# Cam.net
KiCad netlist of a schematic drawn in Altium Designer
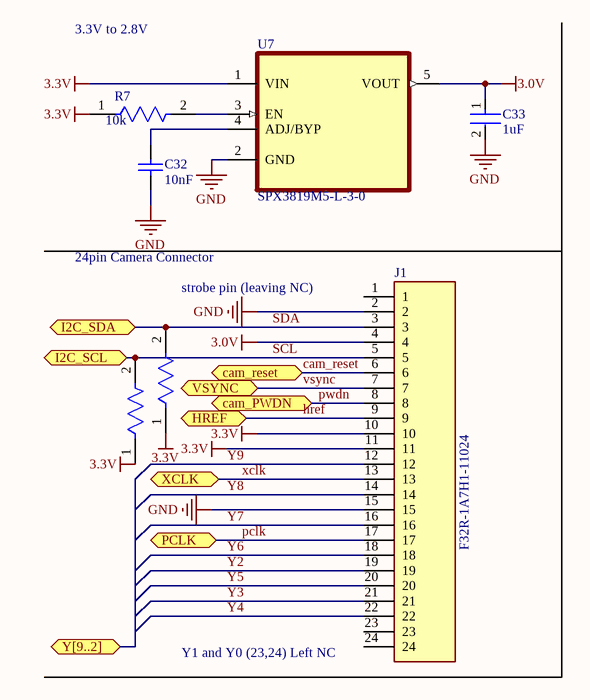
[diagram p0: Cam.SchDoc]

(export (version "E")
  (design (tool "Eeschema 10.0.6"))
  (components
    (comp (ref "C32")
      (value "10nF")
      (footprint "CAPC2013X140X50LL20T25")
      (fields
        (field (name "PART NUMBER") "08055F103KAT2A")
        (field (name "MANUFACTURER") "AVX Interconnect / Elco")
      )
      (libsource (lib "Altium Content Vault") (part "CAP"))
    )
    (comp (ref "C33")
      (value "1uF")
      (footprint "FP-RCE1K1-MFG")
      (description "RCEC72A105K1K1H03B")
      (fields (field (name "TOLERANCE") "10%"))
      (libsource (lib "Altium Content Vault") (part "RCEC72A105K1K1H03B"))
    )
    (comp (ref "J1")
      (value "F32R-1A7H1-11024")
      (footprint "AMPHENOL_F32R-1A7H1-11024")
      (fields (field (name "MF") "Amphenol ICC / Aorora"))
      (libsource (lib "George Evanisko") (part "F32R-1A7H1-11024"))
    )
    (comp (ref "R7")
      (value "10k")
      (footprint "FP-CPF0603-MFG")
      (description "RES SMD 10KΩ 0.5% 1/16W 0603")
      (fields
        (field (name "OCTOPART") "https://octopart.com/cpf0603d10ke-te+connectivity-22737789")
        (field (name "MANUFACTURER") "TE Connectivity")
      )
      (libsource (lib "Altium Content Vault") (part "1029c3af85768c4190bb7ad29bc67b5"))
    )
    (comp (ref "R11")
      (value "AC0603JR-7W10KL")
      (footprint "FP-AC0603-IPC_A")
      (description "RES 10kΩ 5.00% 0.2W 0603")
      (libsource (lib "Altium Content Vault") (part "1029c3af85768c4190bb7ad29bc67b5"))
    )
    (comp (ref "R12")
      (value "AC0603JR-7W10KL")
      (footprint "FP-AC0603-IPC_A")
      (description "RES 10kΩ 5.00% 0.2W 0603")
      (libsource (lib "Altium Content Vault") (part "1029c3af85768c4190bb7ad29bc67b5"))
    )
    (comp (ref "U7")
      (value "SPX3819M5-L-3-0")
      (footprint "SOT95P280X145-5N")
      (description "Linear Voltage Regulator IC Positive Fixed 1 Output 500mA SOT-23-5")
      (fields (field (name "MF") "MaxLinear, Inc."))
      (libsource (lib "George Evanisko") (part "SPX3819M5-L-3-0"))
    )
  )
  (nets
    (net (code "1") (name "/SCL") (class "Default")
      (node (ref "J1") (pin "5") (pinfunction "5_5") (pintype "passive"))
      (node (ref "R11") (pin "2") (pinfunction "2_2") (pintype "passive"))
    )
    (net (code "2") (name "/SDA") (class "Default")
      (node (ref "J1") (pin "3") (pinfunction "3_3") (pintype "passive"))
      (node (ref "R12") (pin "2") (pinfunction "2_2") (pintype "passive"))
    )
    (net (code "3") (name "/Y2") (class "Default")
      (node (ref "J1") (pin "19") (pinfunction "19_19") (pintype "passive"))
    )
    (net (code "4") (name "/Y3") (class "Default")
      (node (ref "J1") (pin "21") (pinfunction "21_21") (pintype "passive"))
    )
    (net (code "5") (name "/Y4") (class "Default")
      (node (ref "J1") (pin "22") (pinfunction "22_22") (pintype "passive"))
    )
    (net (code "6") (name "/Y5") (class "Default")
      (node (ref "J1") (pin "20") (pinfunction "20_20") (pintype "passive"))
    )
    (net (code "7") (name "/Y6") (class "Default")
      (node (ref "J1") (pin "18") (pinfunction "18_18") (pintype "passive"))
    )
    (net (code "8") (name "/Y7") (class "Default")
      (node (ref "J1") (pin "16") (pinfunction "16_16") (pintype "passive"))
    )
    (net (code "9") (name "/Y8") (class "Default")
      (node (ref "J1") (pin "14") (pinfunction "14_14") (pintype "passive"))
    )
    (net (code "10") (name "/Y9") (class "Default")
      (node (ref "J1") (pin "12") (pinfunction "12_12") (pintype "passive"))
    )
    (net (code "12") (name "/cam_reset") (class "Default")
      (node (ref "J1") (pin "6") (pinfunction "6_6") (pintype "passive"))
    )
    (net (code "13") (name "/href") (class "Default")
      (node (ref "J1") (pin "9") (pinfunction "9_9") (pintype "passive"))
    )
    (net (code "14") (name "/pclk") (class "Default")
      (node (ref "J1") (pin "17") (pinfunction "17_17") (pintype "passive"))
    )
    (net (code "15") (name "/pwdn") (class "Default")
      (node (ref "J1") (pin "8") (pinfunction "8_8") (pintype "passive"))
    )
    (net (code "16") (name "/vsync") (class "Default")
      (node (ref "J1") (pin "7") (pinfunction "7_7") (pintype "passive"))
    )
    (net (code "17") (name "/xclk") (class "Default")
      (node (ref "J1") (pin "13") (pinfunction "13_13") (pintype "passive"))
    )
    (net (code "18") (name "3.0V") (class "Default")
      (node (ref "C33") (pin "1") (pinfunction "1_1") (pintype "passive"))
      (node (ref "J1") (pin "4") (pinfunction "4_4") (pintype "passive"))
      (node (ref "U7") (pin "5") (pinfunction "VOUT_5") (pintype "output"))
    )
    (net (code "19") (name "3.3V") (class "Default")
      (node (ref "J1") (pin "10") (pinfunction "10_10") (pintype "passive"))
      (node (ref "J1") (pin "11") (pinfunction "11_11") (pintype "passive"))
      (node (ref "R11") (pin "1") (pinfunction "1_1") (pintype "passive"))
      (node (ref "R12") (pin "1") (pinfunction "1_1") (pintype "passive"))
      (node (ref "R7") (pin "1") (pinfunction "1_1") (pintype "passive"))
      (node (ref "U7") (pin "1") (pinfunction "VIN_1") (pintype "power_in"))
    )
    (net (code "20") (name "GND") (class "Default")
      (node (ref "C32") (pin "2") (pinfunction "2_2") (pintype "passive"))
      (node (ref "C33") (pin "2") (pinfunction "2_2") (pintype "passive"))
      (node (ref "J1") (pin "15") (pinfunction "15_15") (pintype "passive"))
      (node (ref "J1") (pin "2") (pinfunction "2_2") (pintype "passive"))
      (node (ref "U7") (pin "2") (pinfunction "GND_2") (pintype "passive"))
    )
    (net (code "21") (name "Net-(U7-ADJ{slash}BYP)") (class "Default")
      (node (ref "C32") (pin "1") (pinfunction "1_1") (pintype "passive"))
      (node (ref "U7") (pin "4") (pinfunction "ADJ/BYP_4") (pintype "passive"))
    )
    (net (code "22") (name "Net-(U7-EN)") (class "Default")
      (node (ref "R7") (pin "2") (pinfunction "2_2") (pintype "passive"))
      (node (ref "U7") (pin "3") (pinfunction "EN_3") (pintype "input"))
    )
    (net (code "23") (name "unconnected-(J1-Pad1)") (class "Default")
      (node (ref "J1") (pin "1") (pinfunction "1_1") (pintype "passive"))
    )
    (net (code "24") (name "unconnected-(J1-Pad23)") (class "Default")
      (node (ref "J1") (pin "23") (pinfunction "23_23") (pintype "passive"))
    )
    (net (code "25") (name "unconnected-(J1-Pad24)") (class "Default")
      (node (ref "J1") (pin "24") (pinfunction "24_24") (pintype "passive"))
    )
  )
)
